# SOT23-3.net
KiCad netlist of a schematic drawn in EAGLE
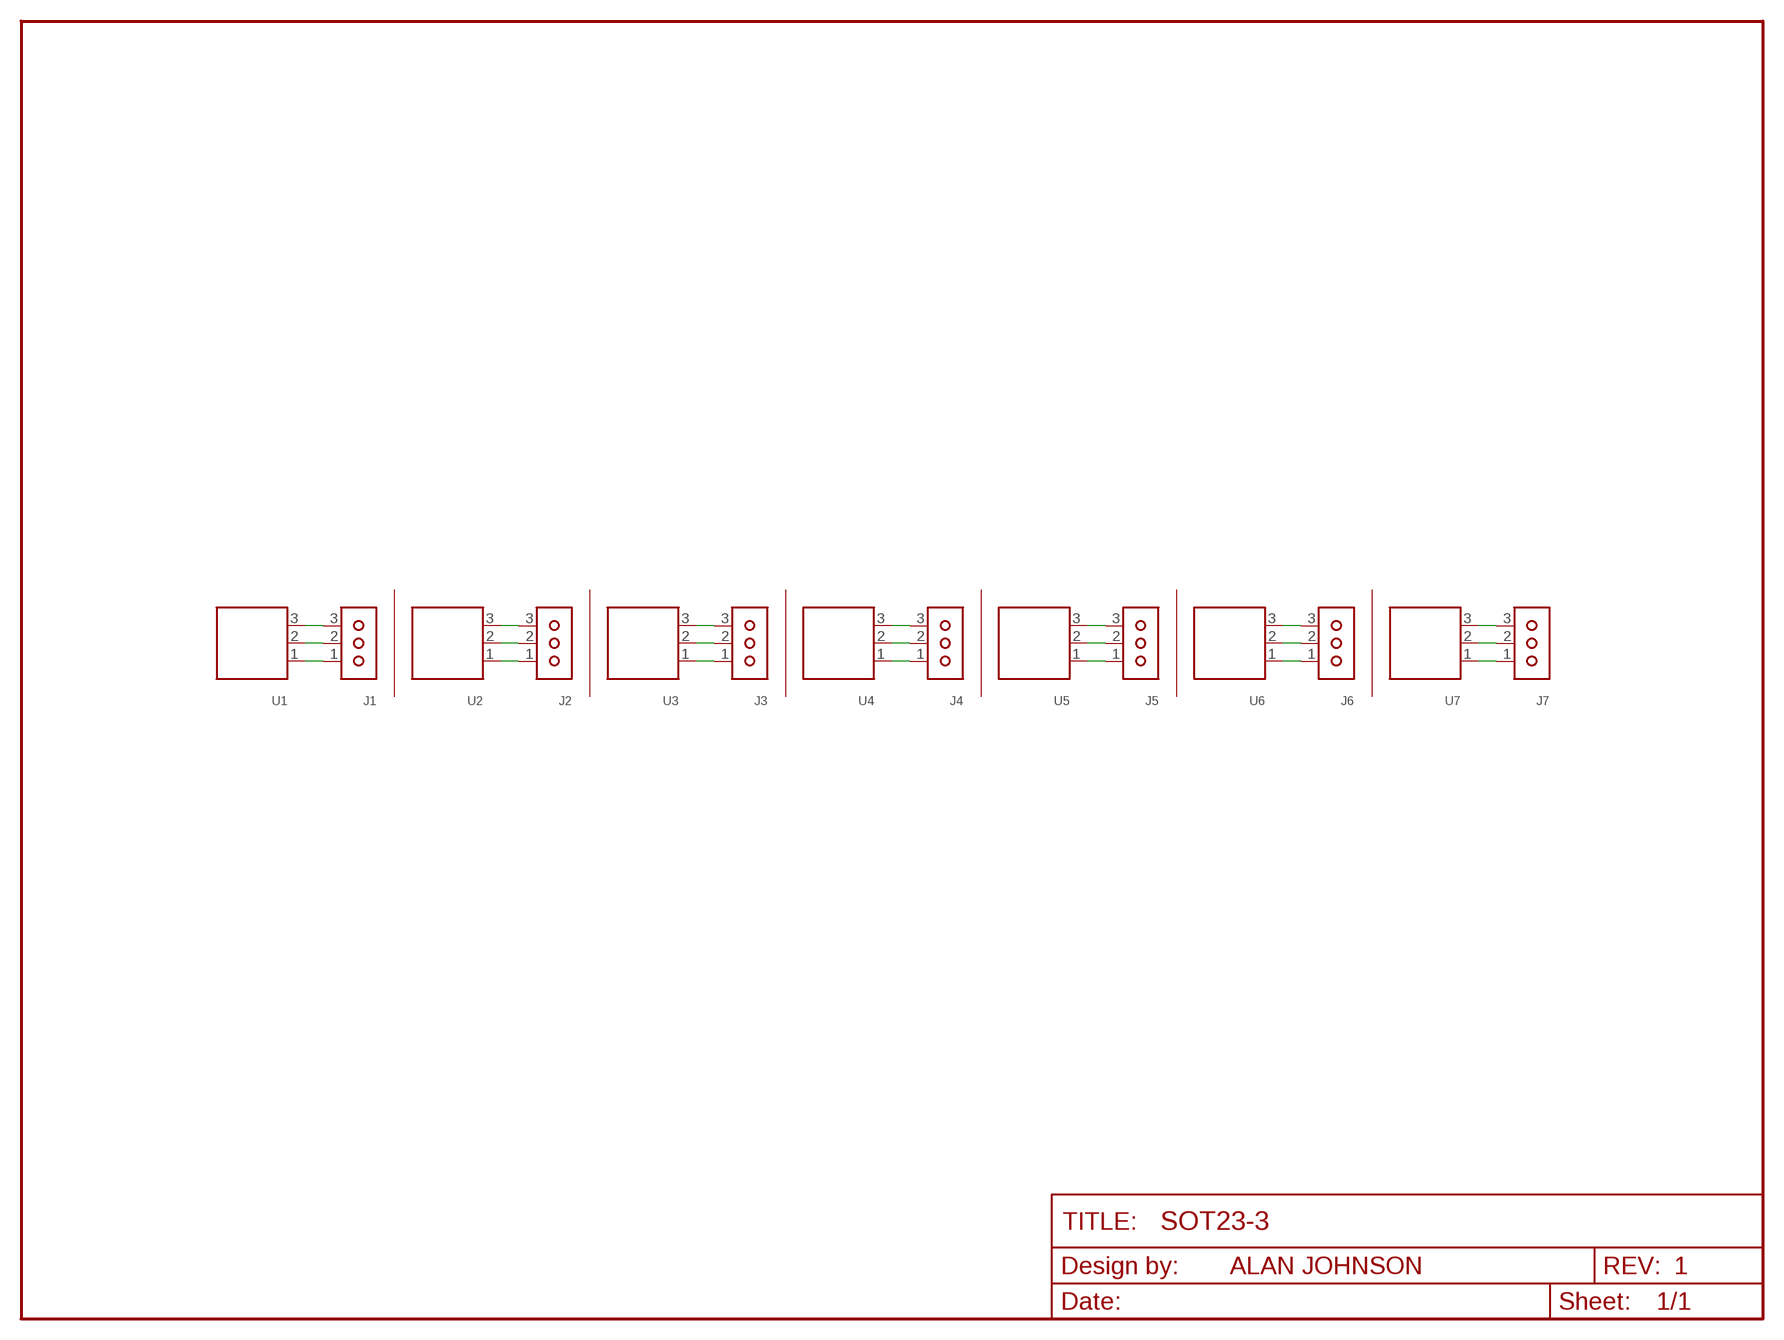
[diagram p0: schematic, sheet 1]

(export (version "E")
  (design (tool "Eeschema 10.0.6"))
  (components
    (comp (ref "J1")
      (value "1X03")
      (footprint "eagle-import:1X03")
      (libsource (lib "eagle-import") (part "1X03"))
    )
    (comp (ref "J2")
      (value "1X03")
      (footprint "eagle-import:1X03")
      (libsource (lib "eagle-import") (part "1X03"))
    )
    (comp (ref "J3")
      (value "1X03")
      (footprint "eagle-import:1X03")
      (libsource (lib "eagle-import") (part "1X03"))
    )
    (comp (ref "J4")
      (value "1X03")
      (footprint "eagle-import:1X03")
      (libsource (lib "eagle-import") (part "1X03"))
    )
    (comp (ref "J5")
      (value "1X03")
      (footprint "eagle-import:1X03")
      (libsource (lib "eagle-import") (part "1X03"))
    )
    (comp (ref "J6")
      (value "1X03")
      (footprint "eagle-import:1X03")
      (libsource (lib "eagle-import") (part "1X03"))
    )
    (comp (ref "J7")
      (value "1X03")
      (footprint "eagle-import:1X03")
      (libsource (lib "eagle-import") (part "1X03"))
    )
    (comp (ref "U1")
      (value "SOT23-3")
      (footprint "eagle-import:SOT23-3")
      (libsource (lib "eagle-import") (part "SOT23-3"))
    )
    (comp (ref "U2")
      (value "SOT23-3")
      (footprint "eagle-import:SOT23-3")
      (libsource (lib "eagle-import") (part "SOT23-3"))
    )
    (comp (ref "U3")
      (value "SOT23-3")
      (footprint "eagle-import:SOT23-3")
      (libsource (lib "eagle-import") (part "SOT23-3"))
    )
    (comp (ref "U4")
      (value "SOT23-3")
      (footprint "eagle-import:SOT23-3")
      (libsource (lib "eagle-import") (part "SOT23-3"))
    )
    (comp (ref "U5")
      (value "SOT23-3")
      (footprint "eagle-import:SOT23-3")
      (libsource (lib "eagle-import") (part "SOT23-3"))
    )
    (comp (ref "U6")
      (value "SOT23-3")
      (footprint "eagle-import:SOT23-3")
      (libsource (lib "eagle-import") (part "SOT23-3"))
    )
    (comp (ref "U7")
      (value "SOT23-3")
      (footprint "eagle-import:SOT23-3")
      (libsource (lib "eagle-import") (part "SOT23-3"))
    )
  )
  (nets
    (net (code "1") (name "Net-(J1-Pad1)") (class "Default")
      (node (ref "J1") (pin "1") (pinfunction "1_1") (pintype "passive"))
      (node (ref "U1") (pin "1") (pinfunction "1_1") (pintype "passive"))
    )
    (net (code "2") (name "Net-(J1-Pad2)") (class "Default")
      (node (ref "J1") (pin "2") (pinfunction "2_2") (pintype "passive"))
      (node (ref "U1") (pin "2") (pinfunction "2_2") (pintype "passive"))
    )
    (net (code "3") (name "Net-(J1-Pad3)") (class "Default")
      (node (ref "J1") (pin "3") (pinfunction "3_3") (pintype "passive"))
      (node (ref "U1") (pin "3") (pinfunction "3_3") (pintype "passive"))
    )
    (net (code "4") (name "Net-(J2-Pad1)") (class "Default")
      (node (ref "J2") (pin "1") (pinfunction "1_1") (pintype "passive"))
      (node (ref "U2") (pin "1") (pinfunction "1_1") (pintype "passive"))
    )
    (net (code "5") (name "Net-(J2-Pad2)") (class "Default")
      (node (ref "J2") (pin "2") (pinfunction "2_2") (pintype "passive"))
      (node (ref "U2") (pin "2") (pinfunction "2_2") (pintype "passive"))
    )
    (net (code "6") (name "Net-(J2-Pad3)") (class "Default")
      (node (ref "J2") (pin "3") (pinfunction "3_3") (pintype "passive"))
      (node (ref "U2") (pin "3") (pinfunction "3_3") (pintype "passive"))
    )
    (net (code "7") (name "Net-(J3-Pad1)") (class "Default")
      (node (ref "J3") (pin "1") (pinfunction "1_1") (pintype "passive"))
      (node (ref "U3") (pin "1") (pinfunction "1_1") (pintype "passive"))
    )
    (net (code "8") (name "Net-(J3-Pad2)") (class "Default")
      (node (ref "J3") (pin "2") (pinfunction "2_2") (pintype "passive"))
      (node (ref "U3") (pin "2") (pinfunction "2_2") (pintype "passive"))
    )
    (net (code "9") (name "Net-(J3-Pad3)") (class "Default")
      (node (ref "J3") (pin "3") (pinfunction "3_3") (pintype "passive"))
      (node (ref "U3") (pin "3") (pinfunction "3_3") (pintype "passive"))
    )
    (net (code "10") (name "Net-(J4-Pad1)") (class "Default")
      (node (ref "J4") (pin "1") (pinfunction "1_1") (pintype "passive"))
      (node (ref "U4") (pin "1") (pinfunction "1_1") (pintype "passive"))
    )
    (net (code "11") (name "Net-(J4-Pad2)") (class "Default")
      (node (ref "J4") (pin "2") (pinfunction "2_2") (pintype "passive"))
      (node (ref "U4") (pin "2") (pinfunction "2_2") (pintype "passive"))
    )
    (net (code "12") (name "Net-(J4-Pad3)") (class "Default")
      (node (ref "J4") (pin "3") (pinfunction "3_3") (pintype "passive"))
      (node (ref "U4") (pin "3") (pinfunction "3_3") (pintype "passive"))
    )
    (net (code "13") (name "Net-(J5-Pad1)") (class "Default")
      (node (ref "J5") (pin "1") (pinfunction "1_1") (pintype "passive"))
      (node (ref "U5") (pin "1") (pinfunction "1_1") (pintype "passive"))
    )
    (net (code "14") (name "Net-(J5-Pad2)") (class "Default")
      (node (ref "J5") (pin "2") (pinfunction "2_2") (pintype "passive"))
      (node (ref "U5") (pin "2") (pinfunction "2_2") (pintype "passive"))
    )
    (net (code "15") (name "Net-(J5-Pad3)") (class "Default")
      (node (ref "J5") (pin "3") (pinfunction "3_3") (pintype "passive"))
      (node (ref "U5") (pin "3") (pinfunction "3_3") (pintype "passive"))
    )
    (net (code "16") (name "Net-(J6-Pad1)") (class "Default")
      (node (ref "J6") (pin "1") (pinfunction "1_1") (pintype "passive"))
      (node (ref "U6") (pin "1") (pinfunction "1_1") (pintype "passive"))
    )
    (net (code "17") (name "Net-(J6-Pad2)") (class "Default")
      (node (ref "J6") (pin "2") (pinfunction "2_2") (pintype "passive"))
      (node (ref "U6") (pin "2") (pinfunction "2_2") (pintype "passive"))
    )
    (net (code "18") (name "Net-(J6-Pad3)") (class "Default")
      (node (ref "J6") (pin "3") (pinfunction "3_3") (pintype "passive"))
      (node (ref "U6") (pin "3") (pinfunction "3_3") (pintype "passive"))
    )
    (net (code "19") (name "Net-(J7-Pad1)") (class "Default")
      (node (ref "J7") (pin "1") (pinfunction "1_1") (pintype "passive"))
      (node (ref "U7") (pin "1") (pinfunction "1_1") (pintype "passive"))
    )
    (net (code "20") (name "Net-(J7-Pad2)") (class "Default")
      (node (ref "J7") (pin "2") (pinfunction "2_2") (pintype "passive"))
      (node (ref "U7") (pin "2") (pinfunction "2_2") (pintype "passive"))
    )
    (net (code "21") (name "Net-(J7-Pad3)") (class "Default")
      (node (ref "J7") (pin "3") (pinfunction "3_3") (pintype "passive"))
      (node (ref "U7") (pin "3") (pinfunction "3_3") (pintype "passive"))
    )
  )
)
